# Power_Supply_V1p1.net
KiCad netlist of a schematic drawn in EAGLE
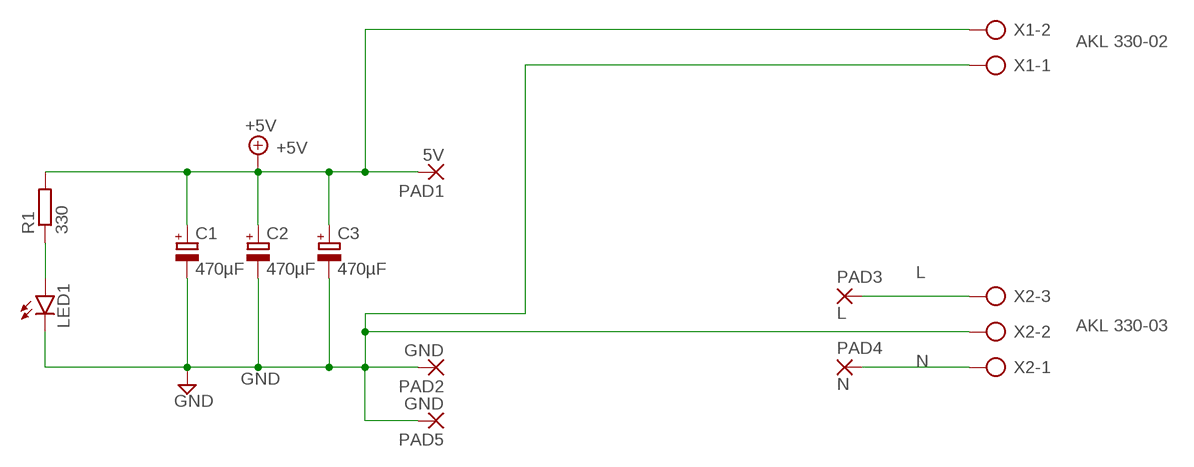
[diagram p0: schematic, sheet 1]

(export (version "E")
  (design (tool "Eeschema 10.0.6"))
  (components
    (comp (ref "C1")
      (value "470µF")
      (footprint "eagle-import:E5-10,5")
      (libsource (lib "eagle-import") (part "CPOL-EUE5-10.5"))
    )
    (comp (ref "C2")
      (value "470µF")
      (footprint "eagle-import:E5-10,5")
      (libsource (lib "eagle-import") (part "CPOL-EUE5-10.5"))
    )
    (comp (ref "C3")
      (value "470µF")
      (footprint "eagle-import:E5-10,5")
      (libsource (lib "eagle-import") (part "CPOL-EUE5-10.5"))
    )
    (comp (ref "LED1")
      (value "LED5MM")
      (footprint "eagle-import:LED5MM")
      (libsource (lib "eagle-import") (part "LED5MM"))
    )
    (comp (ref "PAD1")
      (value "5V")
      (footprint "eagle-import:SMD2,54-5,08")
      (libsource (lib "eagle-import") (part "SMD5"))
    )
    (comp (ref "PAD2")
      (value "GND")
      (footprint "eagle-import:SMD2,54-5,08")
      (libsource (lib "eagle-import") (part "SMD5"))
    )
    (comp (ref "PAD3")
      (value "L")
      (footprint "eagle-import:SMD2,54-5,08")
      (libsource (lib "eagle-import") (part "SMD5"))
    )
    (comp (ref "PAD4")
      (value "N")
      (footprint "eagle-import:SMD2,54-5,08")
      (libsource (lib "eagle-import") (part "SMD5"))
    )
    (comp (ref "PAD5")
      (value "GND")
      (footprint "eagle-import:SMD2,54-5,08")
      (libsource (lib "eagle-import") (part "SMD5"))
    )
    (comp (ref "R1")
      (value "330")
      (footprint "eagle-import:R1206")
      (libsource (lib "eagle-import") (part "R-EU_R1206"))
    )
    (comp (ref "X1")
      (value "AK500/2-H")
      (footprint "eagle-import:AK500_2-H")
      (libsource (lib "eagle-import") (part "AK500/2-H"))
    )
    (comp (ref "X2")
      (value "AK500/3-H")
      (footprint "eagle-import:AK500_3-H")
      (libsource (lib "eagle-import") (part "AK500/3-H"))
    )
  )
  (nets
    (net (code "1") (name "+5V") (class "Default")
      (node (ref "C1") (pin "+") (pinfunction "+_+") (pintype "passive"))
      (node (ref "C2") (pin "+") (pinfunction "+_+") (pintype "passive"))
      (node (ref "C3") (pin "+") (pinfunction "+_+") (pintype "passive"))
      (node (ref "PAD1") (pin "1") (pinfunction "P_1") (pintype "passive"))
      (node (ref "R1") (pin "2") (pinfunction "2_2") (pintype "passive"))
      (node (ref "X1") (pin "2") (pinfunction "KL_2") (pintype "passive"))
    )
    (net (code "2") (name "/L") (class "Default")
      (node (ref "PAD3") (pin "1") (pinfunction "P_1") (pintype "passive"))
      (node (ref "X2") (pin "3") (pinfunction "KL_3") (pintype "passive"))
    )
    (net (code "3") (name "/N") (class "Default")
      (node (ref "PAD4") (pin "1") (pinfunction "P_1") (pintype "passive"))
      (node (ref "X2") (pin "1") (pinfunction "KL_1") (pintype "passive"))
    )
    (net (code "4") (name "GND") (class "Default")
      (node (ref "C1") (pin "-") (pinfunction "-_-") (pintype "passive"))
      (node (ref "C2") (pin "-") (pinfunction "-_-") (pintype "passive"))
      (node (ref "C3") (pin "-") (pinfunction "-_-") (pintype "passive"))
      (node (ref "LED1") (pin "K") (pinfunction "C_K") (pintype "passive"))
      (node (ref "PAD2") (pin "1") (pinfunction "P_1") (pintype "passive"))
      (node (ref "PAD5") (pin "1") (pinfunction "P_1") (pintype "passive"))
      (node (ref "X1") (pin "1") (pinfunction "KL_1") (pintype "passive"))
      (node (ref "X2") (pin "2") (pinfunction "KL_2") (pintype "passive"))
    )
    (net (code "5") (name "Net-(LED1-PadA)") (class "Default")
      (node (ref "LED1") (pin "A") (pinfunction "A_A") (pintype "passive"))
      (node (ref "R1") (pin "1") (pinfunction "1_1") (pintype "passive"))
    )
  )
)
